# MOSFET_IRF540.net
KiCad netlist of a schematic drawn in Altium Designer
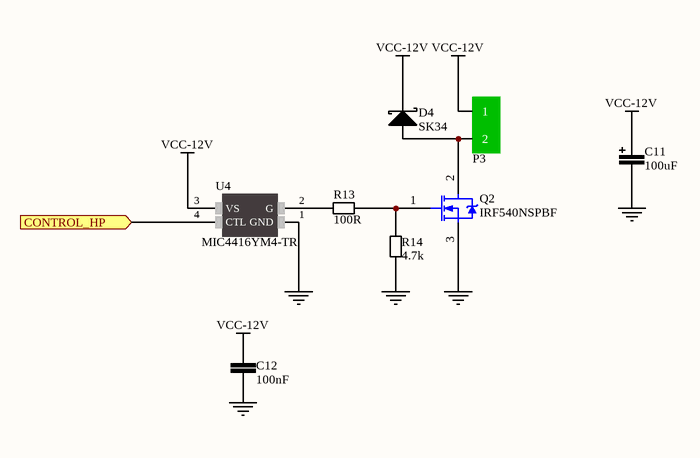
[diagram p0: MOSFET_IRF540.SchDoc]

(export (version "E")
  (design (tool "Eeschema 10.0.6"))
  (components
    (comp (ref "C11")
      (value "100uF")
      (footprint "CAP5X11_RADIAL")
      (description "CAP ALU 4.7u 25V 20%")
      (libsource (lib "Capacitors") (part "00004704"))
    )
    (comp (ref "C12")
      (value "100nF")
      (footprint "CER_0805")
      (description "CAP CER 100n 50V X7R 10% 0805")
      (libsource (lib "Capacitors") (part "00002105"))
    )
    (comp (ref "D4")
      (value "SK34")
      (footprint "DO214AC")
      (description "DIODE SCHOTTKY 40V 3A DO214AC")
      (fields (field (name "MANUFACTURER") "Vishay Semiconductor Diodes Division"))
      (libsource (lib "Discrete_Semiconductor") (part "SK34"))
    )
    (comp (ref "P3")
      (value "DRV_B3")
      (footprint "MOTOR_CON")
      (description "CONNECTOR FOR MOTOR OUTPUT")
      (libsource (lib "Electro_Mechanical") (part "MOT_CONN"))
    )
    (comp (ref "Q2")
      (value "IRF540NSPBF")
      (footprint "D2PAK-2")
      (description "N-MOS")
      (fields (field (name "MANUFACTURER") "INTERNATIONAL RECTIFIER"))
      (libsource (lib "Discrete_Semiconductor") (part "IRF540N"))
    )
    (comp (ref "R13")
      (value "100R")
      (footprint "RESC2013X38N-0805-NOOVERLAY")
      (description "RES SMD 100 Ohm 1/8W 0805")
      (fields (field (name "POWER") "0.125W, 1/8W"))
      (libsource (lib "Resistors") (part "00001000"))
    )
    (comp (ref "R14")
      (value "4.7k")
      (footprint "RESC2013X38N-0805-NOOVERLAY")
      (description "RES SMD 4.7 kOhm 1/8W 0805")
      (fields (field (name "POWER") "0.125W, 1/8W"))
      (libsource (lib "Resistors") (part "00004701"))
    )
    (comp (ref "U4")
      (value "MIC4416YM4-TR")
      (footprint "SOT143-4")
      (description "IC DRIVER MOSF LOW SIDE SOT143-4")
      (libsource (lib "Integrated_circuits") (part "MIC4416"))
    )
  )
  (nets
    (net (code "1") (name "/CONTROL_HP") (class "Default")
      (node (ref "U4") (pin "4") (pinfunction "CTL_4") (pintype "passive"))
    )
    (net (code "2") (name "GND") (class "Default")
      (node (ref "C11") (pin "2") (pinfunction "2_2") (pintype "passive"))
      (node (ref "C12") (pin "1") (pinfunction "1_1") (pintype "passive"))
      (node (ref "Q2") (pin "3") (pinfunction "S_3") (pintype "passive"))
      (node (ref "R14") (pin "1") (pinfunction "1_1") (pintype "passive"))
      (node (ref "U4") (pin "1") (pinfunction "GND_1") (pintype "passive"))
    )
    (net (code "3") (name "Net-(D4-Anode)") (class "Default")
      (node (ref "D4") (pin "2") (pinfunction "Anode_2") (pintype "passive"))
      (node (ref "P3") (pin "2") (pinfunction "2_2") (pintype "passive"))
      (node (ref "Q2") (pin "2") (pinfunction "D_2") (pintype "passive"))
    )
    (net (code "4") (name "Net-(Q2-G)") (class "Default")
      (node (ref "Q2") (pin "1") (pinfunction "G_1") (pintype "passive"))
      (node (ref "R13") (pin "2") (pinfunction "2_2") (pintype "passive"))
      (node (ref "R14") (pin "2") (pinfunction "2_2") (pintype "passive"))
    )
    (net (code "5") (name "Net-(U4-G)") (class "Default")
      (node (ref "R13") (pin "1") (pinfunction "1_1") (pintype "passive"))
      (node (ref "U4") (pin "2") (pinfunction "G_2") (pintype "passive"))
    )
    (net (code "6") (name "VCC-12V") (class "Default")
      (node (ref "C11") (pin "1") (pinfunction "1_1") (pintype "passive"))
      (node (ref "C12") (pin "2") (pinfunction "2_2") (pintype "passive"))
      (node (ref "D4") (pin "1") (pinfunction "Cathode_1") (pintype "passive"))
      (node (ref "P3") (pin "1") (pinfunction "1_1") (pintype "passive"))
      (node (ref "U4") (pin "3") (pinfunction "VS_3") (pintype "passive"))
    )
  )
)
